# IO_FMU3_REV_C.net
KiCad netlist of a schematic drawn in Altium Designer
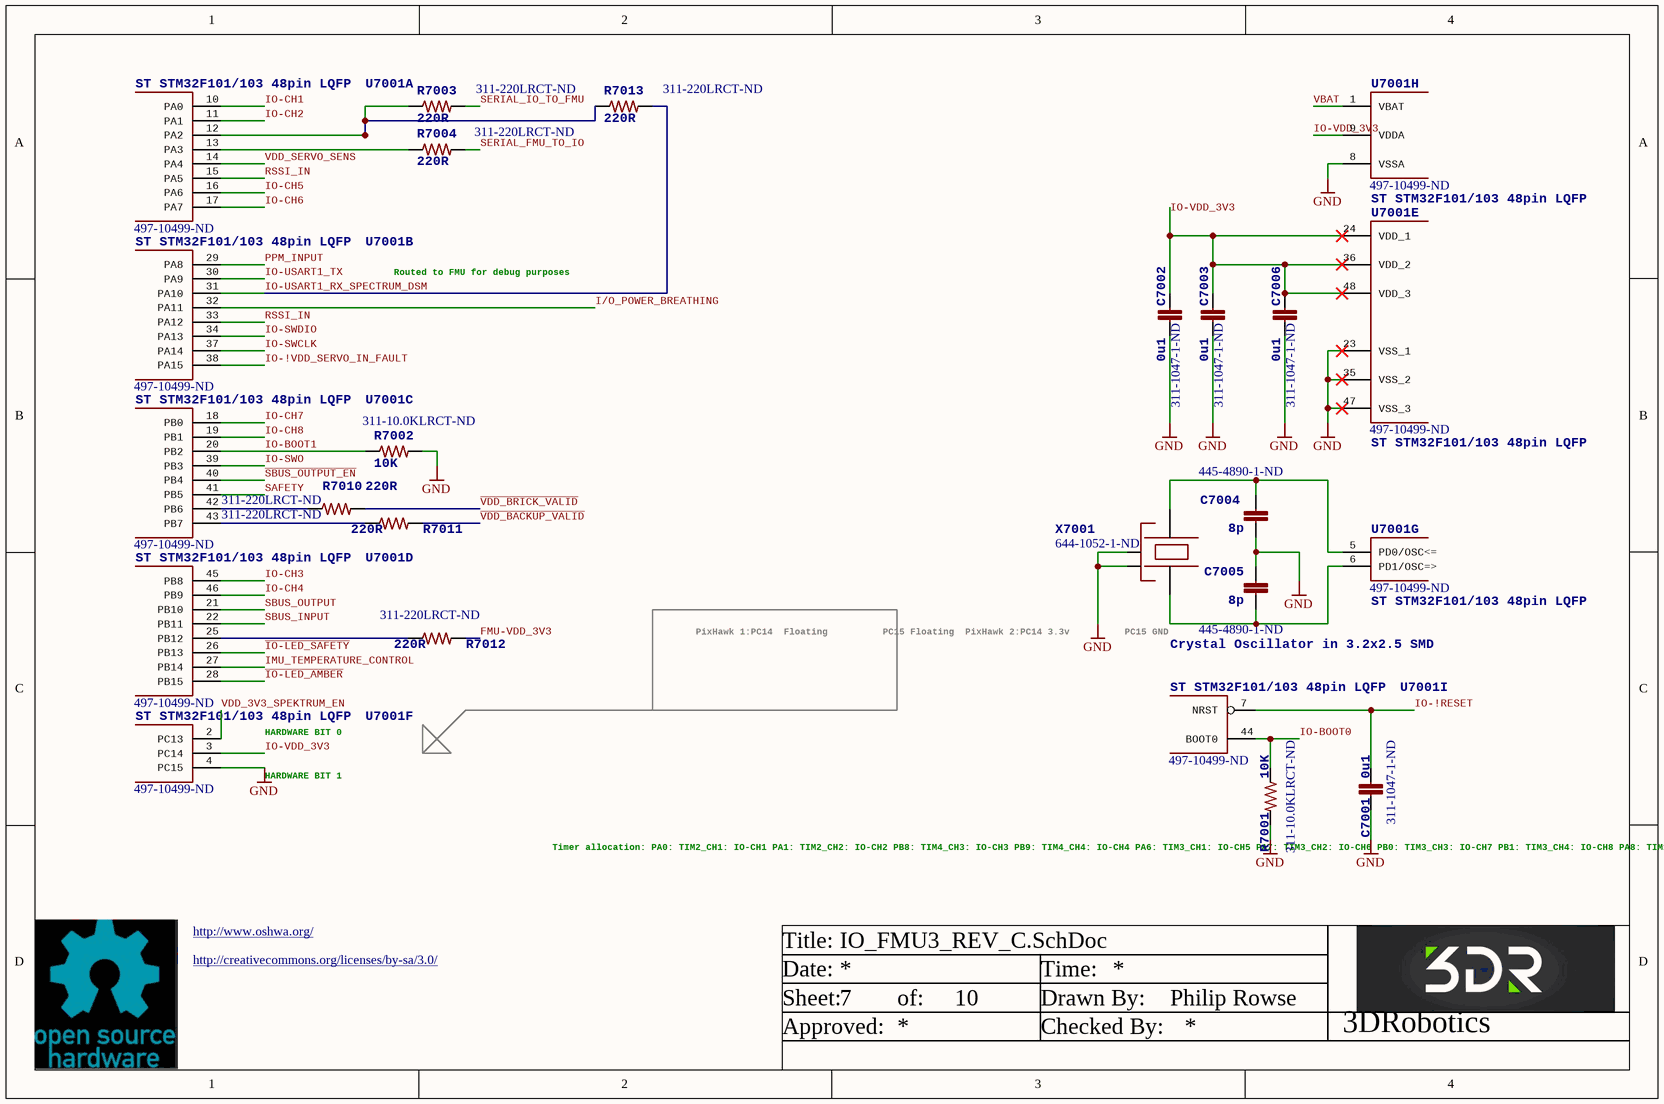
[diagram p0: IO_FMU3_REV_C.SchDoc]

(export (version "E")
  (design (tool "Eeschema 10.0.6"))
  (components
    (comp (ref "C7001")
      (value "0u1")
      (footprint "0402-CAP")
      (description "CAP CER 0.1UF 16V Y5V 0402")
      (fields
        (field (name "PARTNO") "CC0402ZRY5V7BB104")
        (field (name "SUPPLIER PART NUMBER 1") "311-1047-1-ND")
        (field (name "3DR_PARTNO") "ECM0700")
      )
      (libsource (lib "pixhawk2") (part "CAP0402"))
    )
    (comp (ref "C7002")
      (value "0u1")
      (footprint "0402-CAP")
      (description "CAP CER 0.1UF 16V Y5V 0402")
      (fields
        (field (name "PARTNO") "CC0402ZRY5V7BB104")
        (field (name "SUPPLIER PART NUMBER 1") "311-1047-1-ND")
        (field (name "3DR_PARTNO") "ECM0700")
      )
      (libsource (lib "") (part "CAP0402_1"))
    )
    (comp (ref "C7003")
      (value "0u1")
      (footprint "0402-CAP")
      (description "CAP CER 0.1UF 16V Y5V 0402")
      (fields
        (field (name "PARTNO") "CC0402ZRY5V7BB104")
        (field (name "SUPPLIER PART NUMBER 1") "311-1047-1-ND")
        (field (name "3DR_PARTNO") "ECM0700")
      )
      (libsource (lib "") (part "CAP0402_1"))
    )
    (comp (ref "C7004")
      (value "8p")
      (footprint "0402-CAP")
      (description "CAP CER 8PF 50V C0G 0402")
      (fields
        (field (name "PARTNO") "C1005C0G1H080C")
        (field (name "SUPPLIER PART NUMBER 1") "445-4890-1-ND")
        (field (name "3DR_PARTNO") "ECM0710")
      )
      (libsource (lib "") (part "CAP0402_1"))
    )
    (comp (ref "C7005")
      (value "8p")
      (footprint "0402-CAP")
      (description "CAP CER 8PF 50V C0G 0402")
      (fields
        (field (name "PARTNO") "C1005C0G1H080C")
        (field (name "SUPPLIER PART NUMBER 1") "445-4890-1-ND")
        (field (name "3DR_PARTNO") "ECM0710")
      )
      (libsource (lib "") (part "CAP0402_1"))
    )
    (comp (ref "C7006")
      (value "0u1")
      (footprint "0402-CAP")
      (description "CAP CER 0.1UF 16V Y5V 0402")
      (fields
        (field (name "PARTNO") "CC0402ZRY5V7BB104")
        (field (name "SUPPLIER PART NUMBER 1") "311-1047-1-ND")
        (field (name "3DR_PARTNO") "ECM0700")
      )
      (libsource (lib "") (part "CAP0402_1"))
    )
    (comp (ref "R7001")
      (value "10K")
      (footprint "0402-RES")
      (description "RES 10K OHM 1/16W 1% 0402 SMD")
      (fields
        (field (name "PARTNO") "RC0402FR-0710KL")
        (field (name "SUPPLIER PART NUMBER 1") "311-10.0KLRCT-ND")
        (field (name "3DR_PARTNO") "ECM0800")
      )
      (libsource (lib "pixhawk2") (part "RESISTOR0402-RES"))
    )
    (comp (ref "R7002")
      (value "10K")
      (footprint "0402-RES")
      (description "RES 10K OHM 1/16W 1% 0402 SMD")
      (fields
        (field (name "PARTNO") "RC0402FR-0710KL")
        (field (name "SUPPLIER PART NUMBER 1") "311-10.0KLRCT-ND")
        (field (name "3DR_PARTNO") "ECM0800")
      )
      (libsource (lib "pixhawk2") (part "RESISTOR0402-RES"))
    )
    (comp (ref "R7003")
      (value "220R")
      (footprint "0402-RES")
      (description "RES 220 OHM 1/16W 1% 0402 SMD")
      (fields
        (field (name "PARTNO") "RC0402FR-07220RL")
        (field (name "SUPPLIER PART NUMBER 1") "311-220LRCT-ND")
        (field (name "3DR_PARTNO") "ECM0821")
      )
      (libsource (lib "pixhawk2") (part "RESISTOR0402-RES"))
    )
    (comp (ref "R7004")
      (value "220R")
      (footprint "0402-RES")
      (description "RES 220 OHM 1/16W 1% 0402 SMD")
      (fields
        (field (name "PARTNO") "RC0402FR-07220RL")
        (field (name "SUPPLIER PART NUMBER 1") "311-220LRCT-ND")
        (field (name "3DR_PARTNO") "ECM0821")
      )
      (libsource (lib "pixhawk2") (part "RESISTOR0402-RES"))
    )
    (comp (ref "R7010")
      (value "220R")
      (footprint "0402-RES")
      (description "RES 220 OHM 1/16W 1% 0402 SMD")
      (fields
        (field (name "PARTNO") "RC0402FR-07220RL")
        (field (name "SUPPLIER PART NUMBER 1") "311-220LRCT-ND")
        (field (name "3DR_PARTNO") "ECM0821")
      )
      (libsource (lib "pixhawk2") (part "RESISTOR0402-RES"))
    )
    (comp (ref "R7011")
      (value "220R")
      (footprint "0402-RES")
      (description "RES 220 OHM 1/16W 1% 0402 SMD")
      (fields
        (field (name "PARTNO") "RC0402FR-07220RL")
        (field (name "SUPPLIER PART NUMBER 1") "311-220LRCT-ND")
        (field (name "3DR_PARTNO") "ECM0821")
      )
      (libsource (lib "pixhawk2") (part "RESISTOR0402-RES"))
    )
    (comp (ref "R7012")
      (value "220R")
      (footprint "0402-RES")
      (description "RES 220 OHM 1/16W 1% 0402 SMD")
      (fields
        (field (name "PARTNO") "RC0402FR-07220RL")
        (field (name "SUPPLIER PART NUMBER 1") "311-220LRCT-ND")
        (field (name "3DR_PARTNO") "ECM0821")
      )
      (libsource (lib "pixhawk2") (part "RESISTOR0402-RES"))
    )
    (comp (ref "R7013")
      (value "220R")
      (footprint "0402-RES")
      (description "RES 220 OHM 1/16W 1% 0402 SMD")
      (fields
        (field (name "PARTNO") "RC0402FR-07220RL")
        (field (name "SUPPLIER PART NUMBER 1") "311-220LRCT-ND")
        (field (name "3DR_PARTNO") "ECM0821")
      )
      (libsource (lib "pixhawk2") (part "RESISTOR0402-RES"))
    )
    (comp (ref "U7001")
      (value "ST STM32F101/103 48pin LQFP")
      (footprint "TQFP48")
      (description "MCU 32BIT ARM 64K FLASH 48LQFP")
      (fields (field (name "SUPPLIER PART NUMBER 1") "497-10499-ND") (field (name "3DR_PARTNO") "EMC0842"))
      (libsource (lib "pixhawk2") (part "STM32F10XCXT6"))
    )
    (comp (ref "X7001")
      (value "Crystal Oscillator in 3.2x2.5 SMD")
      (footprint "OSCILLATOR-3.2X2.5")
      (description "CRYSTAL 24MHZ 8PF SMD")
      (fields
        (field (name "SUPPLIER PART NUMBER 1") "644-1052-1-ND")
        (field (name "3DR_PARTNO") "ECM0708")
        (field (name "PARTNO") "NX3225SA-24.000MHZ-STD-CSR-1")
      )
      (libsource (lib "pixhawk2") (part "OSCILLATOR-3.2X2.5"))
    )
  )
  (nets
    (net (code "1") (name "/FMU-VDD_3V3") (class "Default")
      (node (ref "R7012") (pin "P$2") (pinfunction "2_P$2") (pintype "passive"))
    )
    (net (code "2") (name "/IMU_TEMPERATURE_CONTROL") (class "Default")
      (node (ref "U7001") (pin "27") (pinfunction "PB14_27") (pintype "passive"))
    )
    (net (code "3") (name "/IO-!RESET") (class "Default")
      (node (ref "C7001") (pin "P$2") (pinfunction "2_P$2") (pintype "passive"))
      (node (ref "U7001") (pin "7") (pinfunction "NRST_7") (pintype "passive"))
    )
    (net (code "4") (name "/IO-!VDD_SERVO_IN_FAULT") (class "Default")
      (node (ref "U7001") (pin "38") (pinfunction "PA15_38") (pintype "passive"))
    )
    (net (code "5") (name "/IO-BOOT0") (class "Default")
      (node (ref "R7001") (pin "P$1") (pinfunction "1_P$1") (pintype "passive"))
      (node (ref "U7001") (pin "44") (pinfunction "BOOT0_44") (pintype "passive"))
    )
    (net (code "6") (name "/IO-BOOT1") (class "Default")
      (node (ref "R7002") (pin "P$1") (pinfunction "1_P$1") (pintype "passive"))
      (node (ref "U7001") (pin "20") (pinfunction "PB2_20") (pintype "passive"))
    )
    (net (code "7") (name "/IO-CH1") (class "Default")
      (node (ref "U7001") (pin "10") (pinfunction "PA0_10") (pintype "passive"))
    )
    (net (code "8") (name "/IO-CH2") (class "Default")
      (node (ref "U7001") (pin "11") (pinfunction "PA1_11") (pintype "passive"))
    )
    (net (code "9") (name "/IO-CH3") (class "Default")
      (node (ref "U7001") (pin "45") (pinfunction "PB8_45") (pintype "passive"))
    )
    (net (code "10") (name "/IO-CH4") (class "Default")
      (node (ref "U7001") (pin "46") (pinfunction "PB9_46") (pintype "passive"))
    )
    (net (code "11") (name "/IO-CH5") (class "Default")
      (node (ref "U7001") (pin "16") (pinfunction "PA6_16") (pintype "passive"))
    )
    (net (code "12") (name "/IO-CH6") (class "Default")
      (node (ref "U7001") (pin "17") (pinfunction "PA7_17") (pintype "passive"))
    )
    (net (code "13") (name "/IO-CH7") (class "Default")
      (node (ref "U7001") (pin "18") (pinfunction "PB0_18") (pintype "passive"))
    )
    (net (code "14") (name "/IO-CH8") (class "Default")
      (node (ref "U7001") (pin "19") (pinfunction "PB1_19") (pintype "passive"))
    )
    (net (code "15") (name "/IO-SWCLK") (class "Default")
      (node (ref "U7001") (pin "37") (pinfunction "PA14_37") (pintype "passive"))
    )
    (net (code "16") (name "/IO-SWDIO") (class "Default")
      (node (ref "U7001") (pin "34") (pinfunction "PA13_34") (pintype "passive"))
    )
    (net (code "17") (name "/IO-SWO") (class "Default")
      (node (ref "U7001") (pin "39") (pinfunction "PB3_39") (pintype "passive"))
    )
    (net (code "18") (name "/IO-USART1_RX_SPECTRUM_DSM") (class "Default")
      (node (ref "R7013") (pin "P$2") (pinfunction "2_P$2") (pintype "passive"))
      (node (ref "U7001") (pin "31") (pinfunction "PA10_31") (pintype "passive"))
    )
    (net (code "19") (name "/IO-USART1_TX") (class "Default")
      (node (ref "U7001") (pin "30") (pinfunction "PA9_30") (pintype "passive"))
    )
    (net (code "20") (name "/IO-VDD_3V3") (class "Default")
      (node (ref "C7002") (pin "P$1") (pinfunction "1_P$1") (pintype "passive"))
      (node (ref "C7003") (pin "P$1") (pinfunction "1_P$1") (pintype "passive"))
      (node (ref "C7006") (pin "P$1") (pinfunction "1_P$1") (pintype "passive"))
      (node (ref "U7001") (pin "24") (pinfunction "VDD_1_24") (pintype "power_in"))
      (node (ref "U7001") (pin "3") (pinfunction "PC14_3") (pintype "passive"))
      (node (ref "U7001") (pin "36") (pinfunction "VDD_2_36") (pintype "power_in"))
      (node (ref "U7001") (pin "48") (pinfunction "VDD_3_48") (pintype "power_in"))
      (node (ref "U7001") (pin "9") (pinfunction "VDDA_9") (pintype "power_in"))
    )
    (net (code "21") (name "/I{slash}O_POWER_BREATHING") (class "Default")
      (node (ref "U7001") (pin "32") (pinfunction "PA11_32") (pintype "passive"))
    )
    (net (code "22") (name "/PPM_INPUT") (class "Default")
      (node (ref "U7001") (pin "29") (pinfunction "PA8_29") (pintype "passive"))
    )
    (net (code "23") (name "/RSSI_IN") (class "Default")
      (node (ref "U7001") (pin "15") (pinfunction "PA5_15") (pintype "passive"))
      (node (ref "U7001") (pin "33") (pinfunction "PA12_33") (pintype "passive"))
    )
    (net (code "24") (name "/SAFETY") (class "Default")
      (node (ref "U7001") (pin "41") (pinfunction "PB5_41") (pintype "passive"))
    )
    (net (code "25") (name "/SBUS_INPUT") (class "Default")
      (node (ref "U7001") (pin "22") (pinfunction "PB11_22") (pintype "passive"))
    )
    (net (code "26") (name "/SBUS_OUTPUT") (class "Default")
      (node (ref "U7001") (pin "21") (pinfunction "PB10_21") (pintype "passive"))
    )
    (net (code "27") (name "/SERIAL_FMU_TO_IO") (class "Default")
      (node (ref "R7004") (pin "P$2") (pinfunction "2_P$2") (pintype "passive"))
    )
    (net (code "28") (name "/SERIAL_IO_TO_FMU") (class "Default")
      (node (ref "R7003") (pin "P$2") (pinfunction "2_P$2") (pintype "passive"))
    )
    (net (code "29") (name "/VBAT") (class "Default")
      (node (ref "U7001") (pin "1") (pinfunction "VBAT_1") (pintype "power_in"))
    )
    (net (code "30") (name "/VDD_3V3_SPEKTRUM_EN") (class "Default")
      (node (ref "U7001") (pin "2") (pinfunction "PC13_2") (pintype "passive"))
    )
    (net (code "31") (name "/VDD_SERVO_SENS") (class "Default")
      (node (ref "U7001") (pin "14") (pinfunction "PA4_14") (pintype "passive"))
    )
    (net (code "32") (name "/~{IO-LED_AMBER}") (class "Default")
      (node (ref "U7001") (pin "28") (pinfunction "PB15_28") (pintype "passive"))
    )
    (net (code "33") (name "/~{IO-LED_SAFETY}") (class "Default")
      (node (ref "U7001") (pin "26") (pinfunction "PB13_26") (pintype "passive"))
    )
    (net (code "34") (name "/~{SBUS_OUTPUT_EN}") (class "Default")
      (node (ref "U7001") (pin "40") (pinfunction "PB4_40") (pintype "passive"))
    )
    (net (code "35") (name "/~{VDD_BACKUP_VALID}") (class "Default")
      (node (ref "R7011") (pin "P$2") (pinfunction "2_P$2") (pintype "passive"))
    )
    (net (code "36") (name "/~{VDD_BRICK_VALID}") (class "Default")
      (node (ref "R7010") (pin "P$2") (pinfunction "2_P$2") (pintype "passive"))
    )
    (net (code "37") (name "GND") (class "Default")
      (node (ref "C7001") (pin "P$1") (pinfunction "1_P$1") (pintype "passive"))
      (node (ref "C7002") (pin "P$2") (pinfunction "2_P$2") (pintype "passive"))
      (node (ref "C7003") (pin "P$2") (pinfunction "2_P$2") (pintype "passive"))
      (node (ref "C7004") (pin "P$2") (pinfunction "2_P$2") (pintype "passive"))
      (node (ref "C7005") (pin "P$1") (pinfunction "1_P$1") (pintype "passive"))
      (node (ref "C7006") (pin "P$2") (pinfunction "2_P$2") (pintype "passive"))
      (node (ref "R7001") (pin "P$2") (pinfunction "2_P$2") (pintype "passive"))
      (node (ref "R7002") (pin "P$2") (pinfunction "2_P$2") (pintype "passive"))
      (node (ref "U7001") (pin "23") (pinfunction "VSS_1_23") (pintype "power_in"))
      (node (ref "U7001") (pin "35") (pinfunction "VSS_2_35") (pintype "power_in"))
      (node (ref "U7001") (pin "4") (pinfunction "PC15_4") (pintype "passive"))
      (node (ref "U7001") (pin "47") (pinfunction "VSS_3_47") (pintype "power_in"))
      (node (ref "U7001") (pin "8") (pinfunction "VSSA_8") (pintype "power_in"))
      (node (ref "X7001") (pin "2") (pinfunction "NC_2_2") (pintype "open_emitter"))
      (node (ref "X7001") (pin "4") (pinfunction "NC_4_4") (pintype "open_emitter"))
    )
    (net (code "38") (name "Net-(C7004-1)") (class "Default")
      (node (ref "C7004") (pin "P$1") (pinfunction "1_P$1") (pintype "passive"))
      (node (ref "U7001") (pin "5") (pinfunction "PD0/OSC<=_5") (pintype "passive"))
      (node (ref "X7001") (pin "3") (pinfunction "3_3") (pintype "passive"))
    )
    (net (code "39") (name "Net-(C7005-2)") (class "Default")
      (node (ref "C7005") (pin "P$2") (pinfunction "2_P$2") (pintype "passive"))
      (node (ref "U7001") (pin "6") (pinfunction "PD1/OSC=>_6") (pintype "passive"))
      (node (ref "X7001") (pin "1") (pinfunction "1_1") (pintype "passive"))
    )
    (net (code "40") (name "Net-(R7003-1)") (class "Default")
      (node (ref "R7003") (pin "P$1") (pinfunction "1_P$1") (pintype "passive"))
      (node (ref "R7013") (pin "P$1") (pinfunction "1_P$1") (pintype "passive"))
      (node (ref "U7001") (pin "12") (pinfunction "PA2_12") (pintype "passive"))
    )
    (net (code "41") (name "Net-(R7004-1)") (class "Default")
      (node (ref "R7004") (pin "P$1") (pinfunction "1_P$1") (pintype "passive"))
      (node (ref "U7001") (pin "13") (pinfunction "PA3_13") (pintype "passive"))
    )
    (net (code "42") (name "Net-(R7010-1)") (class "Default")
      (node (ref "R7010") (pin "P$1") (pinfunction "1_P$1") (pintype "passive"))
      (node (ref "U7001") (pin "42") (pinfunction "PB6_42") (pintype "passive"))
    )
    (net (code "43") (name "Net-(R7011-1)") (class "Default")
      (node (ref "R7011") (pin "P$1") (pinfunction "1_P$1") (pintype "passive"))
      (node (ref "U7001") (pin "43") (pinfunction "PB7_43") (pintype "passive"))
    )
    (net (code "44") (name "Net-(R7012-1)") (class "Default")
      (node (ref "R7012") (pin "P$1") (pinfunction "1_P$1") (pintype "passive"))
      (node (ref "U7001") (pin "25") (pinfunction "PB12_25") (pintype "passive"))
    )
  )
)
